# SERIAL_FMU_REV_1A.net
KiCad netlist of a schematic drawn in Altium Designer
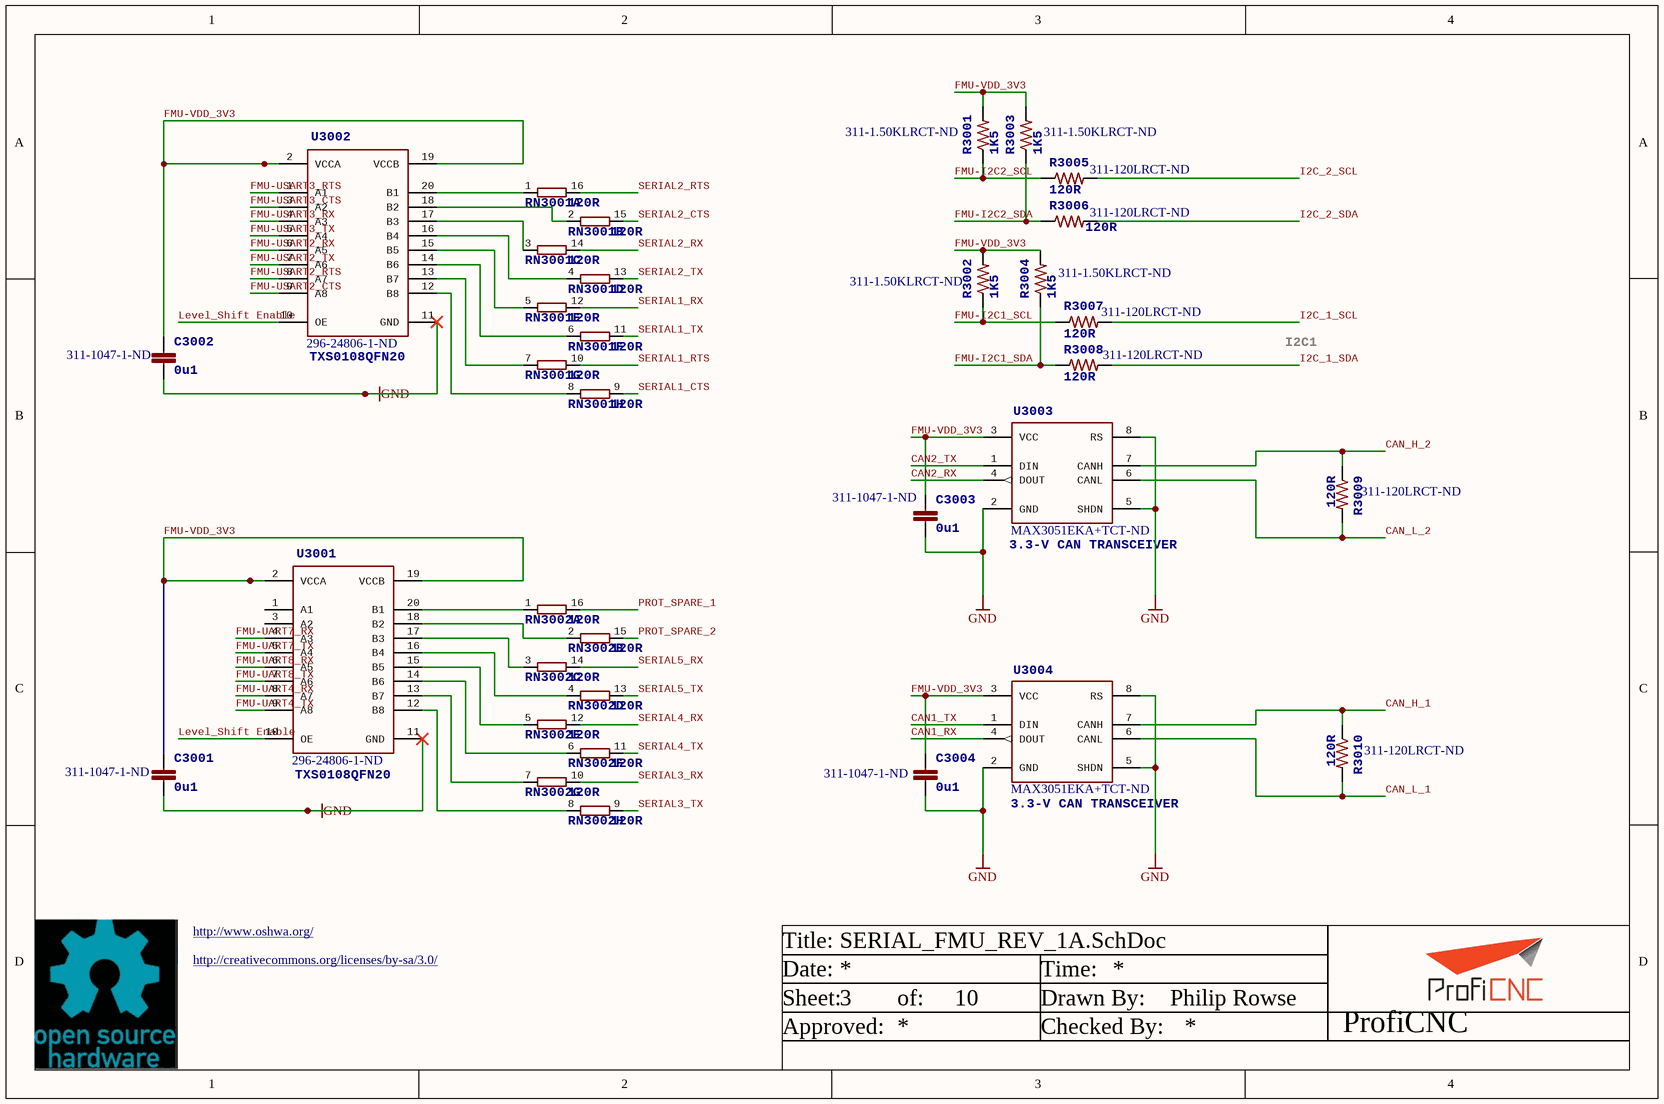
[diagram p0: SERIAL_FMU_REV_1A.SchDoc]

(export (version "E")
  (design (tool "Eeschema 10.0.6"))
  (components
    (comp (ref "C3001")
      (value "0u1")
      (footprint "0402-CAP")
      (description "CAP CER 0.1UF 16V Y5V 0402")
      (fields
        (field (name "PARTNO") "CC0402ZRY5V7BB104")
        (field (name "SUPPLIER PART NUMBER 1") "311-1047-1-ND")
        (field (name "3DR_PARTNO") "ECM0700")
      )
      (libsource (lib "pixhawk2") (part "CAP0402"))
    )
    (comp (ref "C3002")
      (value "0u1")
      (footprint "0402-CAP")
      (description "CAP CER 0.1UF 16V Y5V 0402")
      (fields
        (field (name "PARTNO") "CC0402ZRY5V7BB104")
        (field (name "SUPPLIER PART NUMBER 1") "311-1047-1-ND")
        (field (name "3DR_PARTNO") "ECM0700")
      )
      (libsource (lib "pixhawk2") (part "CAP0402"))
    )
    (comp (ref "C3003")
      (value "0u1")
      (footprint "0402-CAP")
      (description "CAP CER 0.1UF 16V Y5V 0402")
      (fields
        (field (name "PARTNO") "CC0402ZRY5V7BB104")
        (field (name "SUPPLIER PART NUMBER 1") "311-1047-1-ND")
        (field (name "3DR_PARTNO") "ECM0700")
      )
      (libsource (lib "pixhawk2") (part "CAP0402"))
    )
    (comp (ref "C3004")
      (value "0u1")
      (footprint "0402-CAP")
      (description "CAP CER 0.1UF 16V Y5V 0402")
      (fields
        (field (name "PARTNO") "CC0402ZRY5V7BB104")
        (field (name "SUPPLIER PART NUMBER 1") "311-1047-1-ND")
        (field (name "3DR_PARTNO") "ECM0700")
      )
      (libsource (lib "pixhawk2") (part "CAP0402"))
    )
    (comp (ref "R3001")
      (value "1K5")
      (footprint "0402-RES")
      (description "RES 1.5K OHM 1/16W 1% 0402 SMD")
      (fields
        (field (name "PARTNO") "RC0402FR-071K5L")
        (field (name "SUPPLIER PART NUMBER 1") "311-1.50KLRCT-ND")
        (field (name "3DR_PARTNO") "ECM0803")
      )
      (libsource (lib "pixhawk2") (part "RESISTOR0402-RES"))
    )
    (comp (ref "R3002")
      (value "1K5")
      (footprint "0402-RES")
      (description "RES 1.5K OHM 1/16W 1% 0402 SMD")
      (fields
        (field (name "PARTNO") "RC0402FR-071K5L")
        (field (name "SUPPLIER PART NUMBER 1") "311-1.50KLRCT-ND")
        (field (name "3DR_PARTNO") "ECM0803")
      )
      (libsource (lib "pixhawk2") (part "RESISTOR0402-RES"))
    )
    (comp (ref "R3003")
      (value "1K5")
      (footprint "0402-RES")
      (description "RES 1.5K OHM 1/16W 1% 0402 SMD")
      (fields
        (field (name "PARTNO") "RC0402FR-071K5L")
        (field (name "SUPPLIER PART NUMBER 1") "311-1.50KLRCT-ND")
        (field (name "3DR_PARTNO") "ECM0803")
      )
      (libsource (lib "pixhawk2") (part "RESISTOR0402-RES"))
    )
    (comp (ref "R3004")
      (value "1K5")
      (footprint "0402-RES")
      (description "RES 1.5K OHM 1/16W 1% 0402 SMD")
      (fields
        (field (name "PARTNO") "RC0402FR-071K5L")
        (field (name "SUPPLIER PART NUMBER 1") "311-1.50KLRCT-ND")
        (field (name "3DR_PARTNO") "ECM0803")
      )
      (libsource (lib "pixhawk2") (part "RESISTOR0402-RES"))
    )
    (comp (ref "R3005")
      (value "120R")
      (footprint "0402-RES")
      (description "RES 120 OHM 1/16W 1% 0402 SMD")
      (fields
        (field (name "PARTNO") "RC0402FR-07120RL")
        (field (name "SUPPLIER PART NUMBER 1") "311-120LRCT-ND")
        (field (name "3DR_PARTNO") "ECM0820")
      )
      (libsource (lib "pixhawk2") (part "RESISTOR0402-RES"))
    )
    (comp (ref "R3006")
      (value "120R")
      (footprint "0402-RES")
      (description "RES 120 OHM 1/16W 1% 0402 SMD")
      (fields
        (field (name "PARTNO") "RC0402FR-07120RL")
        (field (name "SUPPLIER PART NUMBER 1") "311-120LRCT-ND")
        (field (name "3DR_PARTNO") "ECM0820")
      )
      (libsource (lib "pixhawk2") (part "RESISTOR0402-RES"))
    )
    (comp (ref "R3007")
      (value "120R")
      (footprint "0402-RES")
      (description "RES 120 OHM 1/16W 1% 0402 SMD")
      (fields
        (field (name "PARTNO") "RC0402FR-07120RL")
        (field (name "SUPPLIER PART NUMBER 1") "311-120LRCT-ND")
        (field (name "3DR_PARTNO") "ECM0820")
      )
      (libsource (lib "pixhawk2") (part "RESISTOR0402-RES"))
    )
    (comp (ref "R3008")
      (value "120R")
      (footprint "0402-RES")
      (description "RES 120 OHM 1/16W 1% 0402 SMD")
      (fields
        (field (name "PARTNO") "RC0402FR-07120RL")
        (field (name "SUPPLIER PART NUMBER 1") "311-120LRCT-ND")
        (field (name "3DR_PARTNO") "ECM0820")
      )
      (libsource (lib "pixhawk2") (part "RESISTOR0402-RES"))
    )
    (comp (ref "R3009")
      (value "120R")
      (footprint "0402-RES")
      (description "RES 120 OHM 1/16W 1% 0402 SMD")
      (fields
        (field (name "PARTNO") "RC0402FR-07120RL")
        (field (name "SUPPLIER PART NUMBER 1") "311-120LRCT-ND")
        (field (name "3DR_PARTNO") "ECM0820")
      )
      (libsource (lib "pixhawk2") (part "RESISTOR0402-RES"))
    )
    (comp (ref "R3010")
      (value "120R")
      (footprint "0402-RES")
      (description "RES 120 OHM 1/16W 1% 0402 SMD")
      (fields
        (field (name "PARTNO") "RC0402FR-07120RL")
        (field (name "SUPPLIER PART NUMBER 1") "311-120LRCT-ND")
        (field (name "3DR_PARTNO") "ECM0820")
      )
      (libsource (lib "pixhawk2") (part "RESISTOR0402-RES"))
    )
    (comp (ref "RN3001")
      (value "120R")
      (footprint "EXB2HV")
      (description "RES ARRAY 120 OHM 8 RES 1506")
      (fields (field (name "PARTNO") "EXB-2HV121JV") (field (name "3DR_PARTNO") "EMC"))
      (libsource (lib "pixhawk2") (part "8R-NEXB2HV-120R"))
    )
    (comp (ref "RN3002")
      (value "120R")
      (footprint "EXB2HV")
      (description "RES ARRAY 120 OHM 8 RES 1506")
      (fields (field (name "PARTNO") "EXB-2HV121JV") (field (name "3DR_PARTNO") "EMC"))
      (libsource (lib "pixhawk2") (part "8R-NEXB2HV-120R"))
    )
    (comp (ref "U3001")
      (value "TXS0108QFN20")
      (footprint "QFN20-RGY")
      (description "IC XLATR VOLT-LVL 8B BDIR 20QFN")
      (fields
        (field (name "SUPPLIER PART NUMBER 1") "296-24806-1-ND")
        (field (name "3DR_PARTNO") "ECM0845")
        (field (name "PARTNO") "TXS0108ERGYR")
      )
      (libsource (lib "pixhawk2") (part "TXS0108QFN20"))
    )
    (comp (ref "U3002")
      (value "TXS0108QFN20")
      (footprint "QFN20-RGY")
      (description "IC XLATR VOLT-LVL 8B BDIR 20QFN")
      (fields
        (field (name "SUPPLIER PART NUMBER 1") "296-24806-1-ND")
        (field (name "3DR_PARTNO") "ECM0845")
        (field (name "PARTNO") "TXS0108ERGYR")
      )
      (libsource (lib "pixhawk2") (part "TXS0108QFN20"))
    )
    (comp (ref "U3003")
      (value "3.3-V CAN TRANSCEIVER")
      (footprint "SOT23-8")
      (description "IC TXRX CAN 1MBPS SOT23-8")
      (fields
        (field (name "SUPPLIER PART NUMBER 1") "MAX3051EKA+TCT-ND")
        (field (name "3DR_PARTNO") "ECM0831")
        (field (name "PARTNO") "MAX3051EKA+T")
      )
      (libsource (lib "pixhawk2") (part "MAX3051MAX3051EKA"))
    )
    (comp (ref "U3004")
      (value "3.3-V CAN TRANSCEIVER")
      (footprint "SOT23-8")
      (description "IC TXRX CAN 1MBPS SOT23-8")
      (fields
        (field (name "SUPPLIER PART NUMBER 1") "MAX3051EKA+TCT-ND")
        (field (name "3DR_PARTNO") "ECM0831")
        (field (name "PARTNO") "MAX3051EKA+T")
      )
      (libsource (lib "pixhawk2") (part "MAX3051MAX3051EKA"))
    )
  )
  (nets
    (net (code "1") (name "/CAN1_RX") (class "Default")
      (node (ref "U3004") (pin "4") (pinfunction "DOUT_4") (pintype "output"))
    )
    (net (code "2") (name "/CAN1_TX") (class "Default")
      (node (ref "U3004") (pin "1") (pinfunction "DIN_1") (pintype "passive"))
    )
    (net (code "3") (name "/CAN2_RX") (class "Default")
      (node (ref "U3003") (pin "4") (pinfunction "DOUT_4") (pintype "output"))
    )
    (net (code "4") (name "/CAN2_TX") (class "Default")
      (node (ref "U3003") (pin "1") (pinfunction "DIN_1") (pintype "passive"))
    )
    (net (code "5") (name "/CAN_H_1") (class "Default")
      (node (ref "R3010") (pin "P$1") (pinfunction "1_P$1") (pintype "passive"))
      (node (ref "U3004") (pin "7") (pinfunction "CANH_7") (pintype "passive"))
    )
    (net (code "6") (name "/CAN_H_2") (class "Default")
      (node (ref "R3009") (pin "P$1") (pinfunction "1_P$1") (pintype "passive"))
      (node (ref "U3003") (pin "7") (pinfunction "CANH_7") (pintype "passive"))
    )
    (net (code "7") (name "/CAN_L_1") (class "Default")
      (node (ref "R3010") (pin "P$2") (pinfunction "2_P$2") (pintype "passive"))
      (node (ref "U3004") (pin "6") (pinfunction "CANL_6") (pintype "passive"))
    )
    (net (code "8") (name "/CAN_L_2") (class "Default")
      (node (ref "R3009") (pin "P$2") (pinfunction "2_P$2") (pintype "passive"))
      (node (ref "U3003") (pin "6") (pinfunction "CANL_6") (pintype "passive"))
    )
    (net (code "9") (name "/FMU-I2C1_SCL") (class "Default")
      (node (ref "R3002") (pin "P$1") (pinfunction "1_P$1") (pintype "passive"))
      (node (ref "R3007") (pin "P$1") (pinfunction "1_P$1") (pintype "passive"))
    )
    (net (code "10") (name "/FMU-I2C1_SDA") (class "Default")
      (node (ref "R3004") (pin "P$1") (pinfunction "1_P$1") (pintype "passive"))
      (node (ref "R3008") (pin "P$1") (pinfunction "1_P$1") (pintype "passive"))
    )
    (net (code "11") (name "/FMU-I2C2_SCL") (class "Default")
      (node (ref "R3001") (pin "P$1") (pinfunction "1_P$1") (pintype "passive"))
      (node (ref "R3005") (pin "P$1") (pinfunction "1_P$1") (pintype "passive"))
    )
    (net (code "12") (name "/FMU-I2C2_SDA") (class "Default")
      (node (ref "R3003") (pin "P$1") (pinfunction "1_P$1") (pintype "passive"))
      (node (ref "R3006") (pin "P$1") (pinfunction "1_P$1") (pintype "passive"))
    )
    (net (code "13") (name "/FMU-UART4_RX") (class "Default")
      (node (ref "U3001") (pin "8") (pinfunction "A7_8") (pintype "passive"))
    )
    (net (code "14") (name "/FMU-UART4_TX") (class "Default")
      (node (ref "U3001") (pin "9") (pinfunction "A8_9") (pintype "passive"))
    )
    (net (code "15") (name "/FMU-UART7_RX") (class "Default")
      (node (ref "U3001") (pin "4") (pinfunction "A3_4") (pintype "passive"))
    )
    (net (code "16") (name "/FMU-UART7_TX") (class "Default")
      (node (ref "U3001") (pin "5") (pinfunction "A4_5") (pintype "passive"))
    )
    (net (code "17") (name "/FMU-UART8_RX") (class "Default")
      (node (ref "U3001") (pin "6") (pinfunction "A5_6") (pintype "passive"))
    )
    (net (code "18") (name "/FMU-UART8_TX") (class "Default")
      (node (ref "U3001") (pin "7") (pinfunction "A6_7") (pintype "passive"))
    )
    (net (code "19") (name "/FMU-USART2_CTS") (class "Default")
      (node (ref "U3002") (pin "9") (pinfunction "A8_9") (pintype "passive"))
    )
    (net (code "20") (name "/FMU-USART2_RTS") (class "Default")
      (node (ref "U3002") (pin "8") (pinfunction "A7_8") (pintype "passive"))
    )
    (net (code "21") (name "/FMU-USART2_RX") (class "Default")
      (node (ref "U3002") (pin "6") (pinfunction "A5_6") (pintype "passive"))
    )
    (net (code "22") (name "/FMU-USART2_TX") (class "Default")
      (node (ref "U3002") (pin "7") (pinfunction "A6_7") (pintype "passive"))
    )
    (net (code "23") (name "/FMU-USART3_CTS") (class "Default")
      (node (ref "U3002") (pin "3") (pinfunction "A2_3") (pintype "passive"))
    )
    (net (code "24") (name "/FMU-USART3_RTS") (class "Default")
      (node (ref "U3002") (pin "1") (pinfunction "A1_1") (pintype "passive"))
    )
    (net (code "25") (name "/FMU-USART3_RX") (class "Default")
      (node (ref "U3002") (pin "4") (pinfunction "A3_4") (pintype "passive"))
    )
    (net (code "26") (name "/FMU-USART3_TX") (class "Default")
      (node (ref "U3002") (pin "5") (pinfunction "A4_5") (pintype "passive"))
    )
    (net (code "27") (name "/FMU-VDD_3V3") (class "Default")
      (node (ref "C3001") (pin "P$1") (pinfunction "1_P$1") (pintype "passive"))
      (node (ref "C3002") (pin "P$1") (pinfunction "1_P$1") (pintype "passive"))
      (node (ref "C3003") (pin "P$1") (pinfunction "1_P$1") (pintype "passive"))
      (node (ref "C3004") (pin "P$1") (pinfunction "1_P$1") (pintype "passive"))
      (node (ref "R3001") (pin "P$2") (pinfunction "2_P$2") (pintype "passive"))
      (node (ref "R3002") (pin "P$2") (pinfunction "2_P$2") (pintype "passive"))
      (node (ref "R3003") (pin "P$2") (pinfunction "2_P$2") (pintype "passive"))
      (node (ref "R3004") (pin "P$2") (pinfunction "2_P$2") (pintype "passive"))
      (node (ref "U3001") (pin "19") (pinfunction "VCCB_19") (pintype "passive"))
      (node (ref "U3001") (pin "2") (pinfunction "VCCA_2") (pintype "passive"))
      (node (ref "U3002") (pin "19") (pinfunction "VCCB_19") (pintype "passive"))
      (node (ref "U3002") (pin "2") (pinfunction "VCCA_2") (pintype "passive"))
      (node (ref "U3003") (pin "3") (pinfunction "VCC_3") (pintype "passive"))
      (node (ref "U3004") (pin "3") (pinfunction "VCC_3") (pintype "passive"))
    )
    (net (code "28") (name "/I2C_1_SCL") (class "Default")
      (node (ref "R3007") (pin "P$2") (pinfunction "2_P$2") (pintype "passive"))
    )
    (net (code "29") (name "/I2C_1_SDA") (class "Default")
      (node (ref "R3008") (pin "P$2") (pinfunction "2_P$2") (pintype "passive"))
    )
    (net (code "30") (name "/I2C_2_SCL") (class "Default")
      (node (ref "R3005") (pin "P$2") (pinfunction "2_P$2") (pintype "passive"))
    )
    (net (code "31") (name "/I2C_2_SDA") (class "Default")
      (node (ref "R3006") (pin "P$2") (pinfunction "2_P$2") (pintype "passive"))
    )
    (net (code "32") (name "/Level_Shift Enable") (class "Default")
      (node (ref "U3001") (pin "10") (pinfunction "OE_10") (pintype "passive"))
      (node (ref "U3002") (pin "10") (pinfunction "OE_10") (pintype "passive"))
    )
    (net (code "33") (name "/PROT_SPARE_1") (class "Default")
      (node (ref "RN3002") (pin "16") (pinfunction "2_16") (pintype "passive"))
    )
    (net (code "34") (name "/PROT_SPARE_2") (class "Default")
      (node (ref "RN3002") (pin "15") (pinfunction "2_15") (pintype "passive"))
    )
    (net (code "35") (name "/SERIAL1_CTS") (class "Default")
      (node (ref "RN3001") (pin "9") (pinfunction "2_9") (pintype "passive"))
    )
    (net (code "36") (name "/SERIAL1_RTS") (class "Default")
      (node (ref "RN3001") (pin "10") (pinfunction "2_10") (pintype "passive"))
    )
    (net (code "37") (name "/SERIAL1_RX") (class "Default")
      (node (ref "RN3001") (pin "12") (pinfunction "2_12") (pintype "passive"))
    )
    (net (code "38") (name "/SERIAL1_TX") (class "Default")
      (node (ref "RN3001") (pin "11") (pinfunction "2_11") (pintype "passive"))
    )
    (net (code "39") (name "/SERIAL2_CTS") (class "Default")
      (node (ref "RN3001") (pin "15") (pinfunction "2_15") (pintype "passive"))
    )
    (net (code "40") (name "/SERIAL2_RTS") (class "Default")
      (node (ref "RN3001") (pin "16") (pinfunction "2_16") (pintype "passive"))
    )
    (net (code "41") (name "/SERIAL2_RX") (class "Default")
      (node (ref "RN3001") (pin "14") (pinfunction "2_14") (pintype "passive"))
    )
    (net (code "42") (name "/SERIAL2_TX") (class "Default")
      (node (ref "RN3001") (pin "13") (pinfunction "2_13") (pintype "passive"))
    )
    (net (code "43") (name "/SERIAL3_RX") (class "Default")
      (node (ref "RN3002") (pin "10") (pinfunction "2_10") (pintype "passive"))
    )
    (net (code "44") (name "/SERIAL3_TX") (class "Default")
      (node (ref "RN3002") (pin "9") (pinfunction "2_9") (pintype "passive"))
    )
    (net (code "45") (name "/SERIAL4_RX") (class "Default")
      (node (ref "RN3002") (pin "12") (pinfunction "2_12") (pintype "passive"))
    )
    (net (code "46") (name "/SERIAL4_TX") (class "Default")
      (node (ref "RN3002") (pin "11") (pinfunction "2_11") (pintype "passive"))
    )
    (net (code "47") (name "/SERIAL5_RX") (class "Default")
      (node (ref "RN3002") (pin "14") (pinfunction "2_14") (pintype "passive"))
    )
    (net (code "48") (name "/SERIAL5_TX") (class "Default")
      (node (ref "RN3002") (pin "13") (pinfunction "2_13") (pintype "passive"))
    )
    (net (code "49") (name "GND") (class "Default")
      (node (ref "C3001") (pin "P$2") (pinfunction "2_P$2") (pintype "passive"))
      (node (ref "C3002") (pin "P$2") (pinfunction "2_P$2") (pintype "passive"))
      (node (ref "C3003") (pin "P$2") (pinfunction "2_P$2") (pintype "passive"))
      (node (ref "C3004") (pin "P$2") (pinfunction "2_P$2") (pintype "passive"))
      (node (ref "U3001") (pin "11") (pinfunction "GND_11") (pintype "open_emitter"))
      (node (ref "U3002") (pin "11") (pinfunction "GND_11") (pintype "open_emitter"))
      (node (ref "U3003") (pin "2") (pinfunction "GND_2") (pintype "open_emitter"))
      (node (ref "U3003") (pin "5") (pinfunction "SHDN_5") (pintype "passive"))
      (node (ref "U3003") (pin "8") (pinfunction "RS_8") (pintype "passive"))
      (node (ref "U3004") (pin "2") (pinfunction "GND_2") (pintype "open_emitter"))
      (node (ref "U3004") (pin "5") (pinfunction "SHDN_5") (pintype "passive"))
      (node (ref "U3004") (pin "8") (pinfunction "RS_8") (pintype "passive"))
    )
    (net (code "50") (name "Net-(RN3001B-1)") (class "Default")
      (node (ref "RN3001") (pin "2") (pinfunction "1_2") (pintype "passive"))
      (node (ref "U3002") (pin "18") (pinfunction "B2_18") (pintype "passive"))
    )
    (net (code "51") (name "Net-(RN3001C-1)") (class "Default")
      (node (ref "RN3001") (pin "3") (pinfunction "1_3") (pintype "passive"))
      (node (ref "U3002") (pin "17") (pinfunction "B3_17") (pintype "passive"))
    )
    (net (code "52") (name "Net-(RN3001D-1)") (class "Default")
      (node (ref "RN3001") (pin "4") (pinfunction "1_4") (pintype "passive"))
      (node (ref "U3002") (pin "16") (pinfunction "B4_16") (pintype "passive"))
    )
    (net (code "53") (name "Net-(RN3001E-1)") (class "Default")
      (node (ref "RN3001") (pin "5") (pinfunction "1_5") (pintype "passive"))
      (node (ref "U3002") (pin "15") (pinfunction "B5_15") (pintype "passive"))
    )
    (net (code "54") (name "Net-(RN3001F-1)") (class "Default")
      (node (ref "RN3001") (pin "6") (pinfunction "1_6") (pintype "passive"))
      (node (ref "U3002") (pin "14") (pinfunction "B6_14") (pintype "passive"))
    )
    (net (code "55") (name "Net-(RN3001G-1)") (class "Default")
      (node (ref "RN3001") (pin "7") (pinfunction "1_7") (pintype "passive"))
      (node (ref "U3002") (pin "13") (pinfunction "B7_13") (pintype "passive"))
    )
    (net (code "56") (name "Net-(RN3001H-1)") (class "Default")
      (node (ref "RN3001") (pin "8") (pinfunction "1_8") (pintype "passive"))
      (node (ref "U3002") (pin "12") (pinfunction "B8_12") (pintype "passive"))
    )
    (net (code "57") (name "Net-(RN3002B-1)") (class "Default")
      (node (ref "RN3002") (pin "2") (pinfunction "1_2") (pintype "passive"))
      (node (ref "U3001") (pin "18") (pinfunction "B2_18") (pintype "passive"))
    )
    (net (code "58") (name "Net-(RN3002C-1)") (class "Default")
      (node (ref "RN3002") (pin "3") (pinfunction "1_3") (pintype "passive"))
      (node (ref "U3001") (pin "17") (pinfunction "B3_17") (pintype "passive"))
    )
    (net (code "59") (name "Net-(RN3002D-1)") (class "Default")
      (node (ref "RN3002") (pin "4") (pinfunction "1_4") (pintype "passive"))
      (node (ref "U3001") (pin "16") (pinfunction "B4_16") (pintype "passive"))
    )
    (net (code "60") (name "Net-(RN3002E-1)") (class "Default")
      (node (ref "RN3002") (pin "5") (pinfunction "1_5") (pintype "passive"))
      (node (ref "U3001") (pin "15") (pinfunction "B5_15") (pintype "passive"))
    )
    (net (code "61") (name "Net-(RN3002F-1)") (class "Default")
      (node (ref "RN3002") (pin "6") (pinfunction "1_6") (pintype "passive"))
      (node (ref "U3001") (pin "14") (pinfunction "B6_14") (pintype "passive"))
    )
    (net (code "62") (name "Net-(RN3002G-1)") (class "Default")
      (node (ref "RN3002") (pin "7") (pinfunction "1_7") (pintype "passive"))
      (node (ref "U3001") (pin "13") (pinfunction "B7_13") (pintype "passive"))
    )
    (net (code "63") (name "Net-(RN3002H-1)") (class "Default")
      (node (ref "RN3002") (pin "8") (pinfunction "1_8") (pintype "passive"))
      (node (ref "U3001") (pin "12") (pinfunction "B8_12") (pintype "passive"))
    )
    (net (code "64") (name "Net-(U3001-B1)") (class "Default")
      (node (ref "RN3002") (pin "1") (pinfunction "1_1") (pintype "passive"))
      (node (ref "U3001") (pin "20") (pinfunction "B1_20") (pintype "passive"))
    )
    (net (code "65") (name "Net-(U3002-B1)") (class "Default")
      (node (ref "RN3001") (pin "1") (pinfunction "1_1") (pintype "passive"))
      (node (ref "U3002") (pin "20") (pinfunction "B1_20") (pintype "passive"))
    )
    (net (code "66") (name "unconnected-(U3001-A1-Pad1)") (class "Default")
      (node (ref "U3001") (pin "1") (pinfunction "A1_1") (pintype "passive"))
    )
    (net (code "67") (name "unconnected-(U3001-A2-Pad3)") (class "Default")
      (node (ref "U3001") (pin "3") (pinfunction "A2_3") (pintype "passive"))
    )
  )
)
